# schematic.net
KiCad netlist of a schematic drawn in Altium Designer
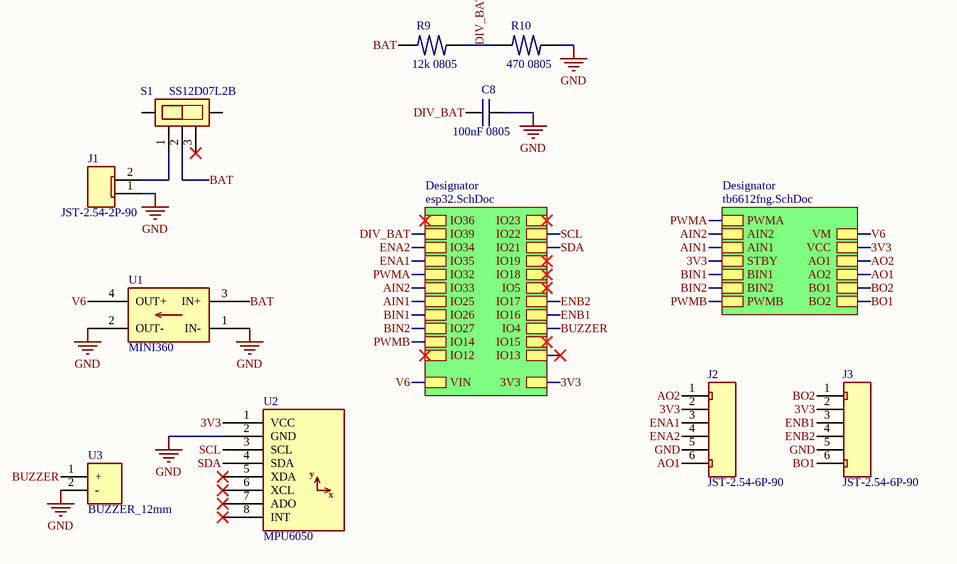
[diagram p0: schematic.SchDoc]

(export (version "E")
  (design (tool "Eeschema 10.0.6"))
  (components
    (comp (ref "C8")
      (value "100nF 0805")
      (footprint "CAPACITOR 0805")
      (description "Generic Capacitor 0805, 2x1.25x1.4mm.")
      (libsource (lib "Ceramic Capacitor") (part "CAPACITOR 0805"))
    )
    (comp (ref "J1")
      (value "JST-2.54-2P-90")
      (footprint "JST-2.54-2P-90")
      (description "Female Connector JST 2 Vias, 2.54mm 90º.")
      (libsource (lib "Connectors") (part "JST-2.54-2P-90"))
    )
    (comp (ref "J2")
      (value "JST-2.54-6P-90")
      (footprint "JST-2.54-6P-90")
      (description "Female Connector JST 6 Vias, 2.54mm 90º.")
      (libsource (lib "Connectors") (part "JST-2.54-6P-90"))
    )
    (comp (ref "J3")
      (value "JST-2.54-6P-90")
      (footprint "JST-2.54-6P-90")
      (description "Female Connector JST 6 Vias, 2.54mm 90º.")
      (libsource (lib "Connectors") (part "JST-2.54-6P-90"))
    )
    (comp (ref "R9")
      (value "12k 0805")
      (footprint "RESISTOR_0805")
      (libsource (lib "Resistors") (part "RESISTOR_0805"))
    )
    (comp (ref "R10")
      (value "470 0805")
      (footprint "RESISTOR_0805")
      (libsource (lib "Resistors") (part "RESISTOR_0805"))
    )
    (comp (ref "S1")
      (value "SS12D07L2B")
      (footprint "SS12D07L2B")
      (description "Vertical Slide Switch 5 Pins 8.7x4.5x4.7mm.")
      (libsource (lib "Buttons & Switches") (part "SS12D07L2B"))
    )
    (comp (ref "U1")
      (value "MINI360")
      (footprint "MINI360")
      (description "MODULE BUCK STEP DOWN 3A 18x12mm")
      (libsource (lib "Voltage Regulators") (part "MINI360"))
    )
    (comp (ref "U2")
      (value "MPU6050")
      (footprint "MPU6050")
      (description "IMU ACCEL/GYRO 3-AXIS I2C")
      (libsource (lib "Sensors") (part "MPU6050"))
    )
    (comp (ref "U3")
      (value "BUZZER_12mm")
      (footprint "BUZZER_12mm")
      (description "BUZZER MAGNETIC 12MM")
      (libsource (lib "Random") (part "BUZZER_12mm"))
    )
  )
  (nets
    (net (code "1") (name "/3V3") (class "Default")
      (node (ref "J2") (pin "2") (pintype "passive"))
      (node (ref "J3") (pin "2") (pintype "passive"))
      (node (ref "U2") (pin "1") (pinfunction "VCC_1") (pintype "passive"))
    )
    (net (code "4") (name "/AO1") (class "Default") (node (ref "J2") (pin "6") (pintype "passive")))
    (net (code "5") (name "/AO2") (class "Default") (node (ref "J2") (pin "1") (pintype "passive")))
    (net (code "6") (name "/BAT") (class "Default")
      (node (ref "R9") (pin "2") (pinfunction "2_2") (pintype "passive"))
      (node (ref "S1") (pin "2") (pinfunction "2_2") (pintype "passive"))
      (node (ref "U1") (pin "3") (pinfunction "IN+_3") (pintype "passive"))
    )
    (net (code "9") (name "/BO1") (class "Default") (node (ref "J3") (pin "6") (pintype "passive")))
    (net (code "10") (name "/BO2") (class "Default") (node (ref "J3") (pin "1") (pintype "passive")))
    (net (code "11") (name "/BUZZER") (class "Default")
      (node (ref "U3") (pin "1") (pinfunction "+_1") (pintype "passive"))
    )
    (net (code "12") (name "/DIV_BAT") (class "Default")
      (node (ref "C8") (pin "1") (pinfunction "1_1") (pintype "passive"))
      (node (ref "R10") (pin "2") (pinfunction "2_2") (pintype "passive"))
      (node (ref "R9") (pin "1") (pinfunction "1_1") (pintype "passive"))
    )
    (net (code "13") (name "/ENA1") (class "Default") (node (ref "J2") (pin "3") (pintype "passive")))
    (net (code "14") (name "/ENA2") (class "Default") (node (ref "J2") (pin "4") (pintype "passive")))
    (net (code "15") (name "/ENB1") (class "Default") (node (ref "J3") (pin "3") (pintype "passive")))
    (net (code "16") (name "/ENB2") (class "Default") (node (ref "J3") (pin "4") (pintype "passive")))
    (net (code "27") (name "/SCL") (class "Default")
      (node (ref "U2") (pin "3") (pinfunction "SCL_3") (pintype "passive"))
    )
    (net (code "28") (name "/SDA") (class "Default")
      (node (ref "U2") (pin "4") (pinfunction "SDA_4") (pintype "passive"))
    )
    (net (code "29") (name "/V6") (class "Default")
      (node (ref "U1") (pin "4") (pinfunction "OUT+_4") (pintype "passive"))
    )
    (net (code "30") (name "GND") (class "Default")
      (node (ref "C8") (pin "2") (pinfunction "2_2") (pintype "passive"))
      (node (ref "J1") (pin "1") (pintype "passive"))
      (node (ref "J2") (pin "5") (pintype "passive"))
      (node (ref "J3") (pin "5") (pintype "passive"))
      (node (ref "R10") (pin "1") (pinfunction "1_1") (pintype "passive"))
      (node (ref "U1") (pin "1") (pinfunction "IN-_1") (pintype "passive"))
      (node (ref "U1") (pin "2") (pinfunction "OUT-_2") (pintype "passive"))
      (node (ref "U2") (pin "2") (pinfunction "GND_2") (pintype "passive"))
      (node (ref "U3") (pin "2") (pinfunction "-_2") (pintype "passive"))
    )
    (net (code "31") (name "Net-(J1-Pad2)") (class "Default")
      (node (ref "J1") (pin "2") (pintype "passive"))
      (node (ref "S1") (pin "1") (pinfunction "1_1") (pintype "passive"))
    )
    (net (code "32") (name "unconnected-(S1-Pad3)") (class "Default")
      (node (ref "S1") (pin "3") (pinfunction "3_3") (pintype "passive+no_connect"))
    )
    (net (code "33") (name "unconnected-(U2-ADO-Pad7)") (class "Default")
      (node (ref "U2") (pin "7") (pinfunction "ADO_7") (pintype "passive+no_connect"))
    )
    (net (code "34") (name "unconnected-(U2-INT-Pad8)") (class "Default")
      (node (ref "U2") (pin "8") (pinfunction "INT_8") (pintype "passive+no_connect"))
    )
    (net (code "35") (name "unconnected-(U2-XCL-Pad6)") (class "Default")
      (node (ref "U2") (pin "6") (pinfunction "XCL_6") (pintype "passive+no_connect"))
    )
    (net (code "36") (name "unconnected-(U2-XDA-Pad5)") (class "Default")
      (node (ref "U2") (pin "5") (pinfunction "XDA_5") (pintype "passive+no_connect"))
    )
  )
)
